# EFUSE_TPS259460A_as_switch.net
KiCad netlist of a schematic drawn in Altium Designer
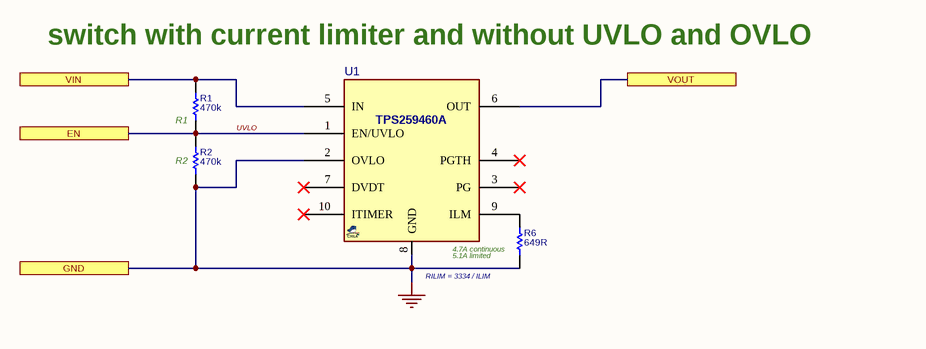
[diagram p0: EFUSE_TPS259460A_as_switch.SchDoc]

(export (version "E")
  (design (tool "Eeschema 10.0.6"))
  (components
    (comp (ref "R1")
      (value "470k")
      (footprint "R0402A")
      (description "RESISTOR, SMD")
      (libsource (lib "passive_res_smd") (part "RES_SMD"))
    )
    (comp (ref "R2")
      (value "470k")
      (footprint "R0402A")
      (description "RESISTOR, SMD")
      (libsource (lib "passive_res_smd") (part "RES_SMD"))
    )
    (comp (ref "R6")
      (value "649R")
      (footprint "R0402")
      (description "RESISTOR, SMD")
      (libsource (lib "passive_res_smd") (part "RES_SMD"))
    )
    (comp (ref "U1")
      (value "TPS259460A")
      (footprint "QFN45_10_2020_RPW")
      (description "LOAD SW, 2.7~23V eFuse, 0.5~6A, 28mOhm, OVP+UVLO, autoretry")
      (fields (field (name "MANF") "TI") (field (name "MANF_P#") "TPS259460ARPW"))
      (libsource (lib "power_load_switch") (part "TPS259460A_QFN10"))
    )
  )
  (nets
    (net (code "1") (name "/UVLO") (class "Default")
      (node (ref "R1") (pin "1") (pinfunction "1_1") (pintype "passive"))
      (node (ref "R2") (pin "2") (pinfunction "2_2") (pintype "passive"))
      (node (ref "U1") (pin "1") (pinfunction "EN/UVLO_1") (pintype "passive"))
    )
    (net (code "2") (name "/VIN") (class "Default")
      (node (ref "R1") (pin "2") (pinfunction "2_2") (pintype "passive"))
      (node (ref "U1") (pin "5") (pinfunction "IN_5") (pintype "passive"))
    )
    (net (code "3") (name "/VOUT") (class "Default")
      (node (ref "U1") (pin "6") (pinfunction "OUT_6") (pintype "passive"))
    )
    (net (code "4") (name "GND") (class "Default")
      (node (ref "R2") (pin "1") (pinfunction "1_1") (pintype "passive"))
      (node (ref "R6") (pin "1") (pinfunction "1_1") (pintype "passive"))
      (node (ref "U1") (pin "2") (pinfunction "OVLO_2") (pintype "passive"))
      (node (ref "U1") (pin "8") (pinfunction "GND_8") (pintype "passive"))
    )
    (net (code "5") (name "Net-(U1-ILM)") (class "Default")
      (node (ref "R6") (pin "2") (pinfunction "2_2") (pintype "passive"))
      (node (ref "U1") (pin "9") (pinfunction "ILM_9") (pintype "passive"))
    )
    (net (code "6") (name "unconnected-(U1-DVDT-Pad7)") (class "Default")
      (node (ref "U1") (pin "7") (pinfunction "DVDT_7") (pintype "passive+no_connect"))
    )
    (net (code "7") (name "unconnected-(U1-ITIMER-Pad10)") (class "Default")
      (node (ref "U1") (pin "10") (pinfunction "ITIMER_10") (pintype "passive+no_connect"))
    )
    (net (code "8") (name "unconnected-(U1-PG-Pad3)") (class "Default")
      (node (ref "U1") (pin "3") (pinfunction "PG_3") (pintype "passive+no_connect"))
    )
    (net (code "9") (name "unconnected-(U1-PGTH-Pad4)") (class "Default")
      (node (ref "U1") (pin "4") (pinfunction "PGTH_4") (pintype "passive+no_connect"))
    )
  )
)
